# OLED.net
KiCad netlist of a schematic drawn in EAGLE
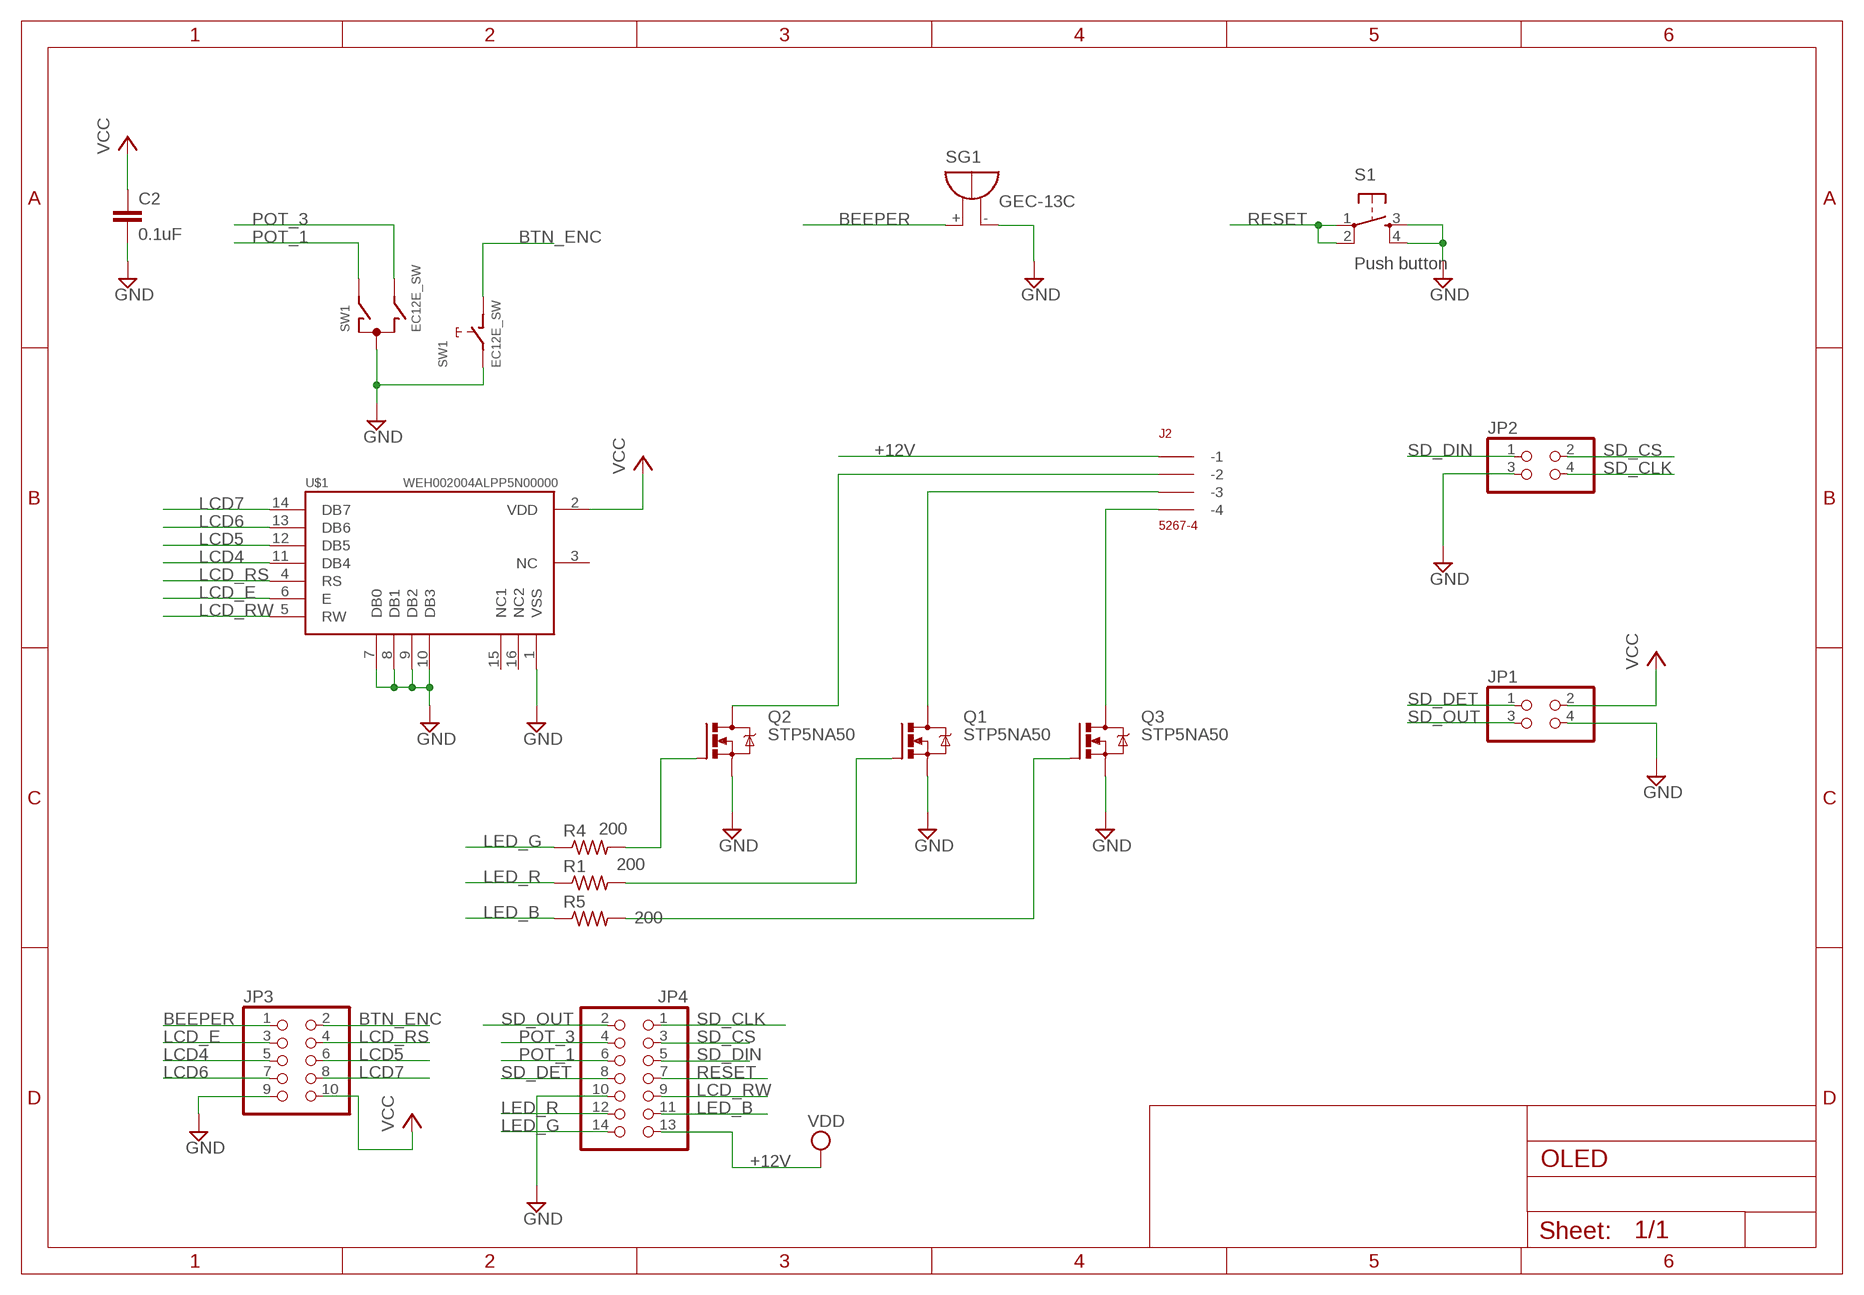
[diagram p0: schematic, sheet 1]

(export (version "E")
  (design (tool "Eeschema 10.0.6"))
  (components
    (comp (ref "C2")
      (value "0.1uF")
      (footprint "eagle-import:C0805")
      (libsource (lib "eagle-import") (part "C-EUC0805"))
    )
    (comp (ref "J2")
      (value "5267-4")
      (footprint "eagle-import:5267-4")
      (libsource (lib "eagle-import") (part "5267-4"))
    )
    (comp (ref "JP1")
      (value "PINHD-2X2")
      (footprint "eagle-import:2X02")
      (libsource (lib "eagle-import") (part "PINHD-2X2"))
    )
    (comp (ref "JP2")
      (value "PINHD-2X2")
      (footprint "eagle-import:2X02")
      (libsource (lib "eagle-import") (part "PINHD-2X2"))
    )
    (comp (ref "JP3")
      (value "PINHD-2X5/90")
      (footprint "eagle-import:2X05_90")
      (libsource (lib "eagle-import") (part "PINHD-2X5/90"))
    )
    (comp (ref "JP4")
      (value "PINHD-2X7/90")
      (footprint "eagle-import:2X07_90")
      (libsource (lib "eagle-import") (part "PINHD-2X7/90"))
    )
    (comp (ref "Q1")
      (value "STP5NA50")
      (footprint "eagle-import:TO220BV")
      (libsource (lib "eagle-import") (part "STP5NA50"))
    )
    (comp (ref "Q2")
      (value "STP5NA50")
      (footprint "eagle-import:TO220BV")
      (libsource (lib "eagle-import") (part "STP5NA50"))
    )
    (comp (ref "Q3")
      (value "STP5NA50")
      (footprint "eagle-import:TO220BV")
      (libsource (lib "eagle-import") (part "STP5NA50"))
    )
    (comp (ref "R1")
      (value "200")
      (footprint "eagle-import:R2012")
      (libsource (lib "eagle-import") (part "R-US_R2012"))
    )
    (comp (ref "R4")
      (value "200")
      (footprint "eagle-import:R2012")
      (libsource (lib "eagle-import") (part "R-US_R2012"))
    )
    (comp (ref "R5")
      (value "200")
      (footprint "eagle-import:R2012")
      (libsource (lib "eagle-import") (part "R-US_R2012"))
    )
    (comp (ref "S1")
      (value "Push button")
      (footprint "eagle-import:TACTILE-PTH")
      (libsource (lib "eagle-import") (part "TAC_SWITCHPTH"))
    )
    (comp (ref "SG1")
      (value "GEC-13C")
      (footprint "eagle-import:F_TMB")
      (libsource (lib "eagle-import") (part "F/TMB"))
    )
    (comp (ref "SW1")
      (value "EC12E_SW")
      (footprint "eagle-import:ALPS_EC12E_SW")
      (fields (field (name "MPN") "EC12E2424407"))
      (libsource (lib "eagle-import") (part "EC12E_SW"))
    )
    (comp (ref "U$1")
      (value "OLED")
      (footprint "eagle-import:WEH002004ALPP5N00000")
      (libsource (lib "eagle-import") (part "OLED"))
    )
  )
  (nets
    (net (code "1") (name "/BEEPER") (class "Default")
      (node (ref "JP3") (pin "1") (pinfunction "1_1") (pintype "passive"))
      (node (ref "SG1") (pin "+") (pinfunction "+_+") (pintype "passive"))
    )
    (net (code "2") (name "/BTN_ENC") (class "Default")
      (node (ref "JP3") (pin "2") (pinfunction "2_2") (pintype "passive"))
      (node (ref "SW1") (pin "D") (pinfunction "1_D") (pintype "passive"))
    )
    (net (code "3") (name "/LCD4") (class "Default")
      (node (ref "JP3") (pin "5") (pinfunction "5_5") (pintype "passive"))
      (node (ref "U$1") (pin "11") (pinfunction "DB4_11") (pintype "bidirectional"))
    )
    (net (code "4") (name "/LCD5") (class "Default")
      (node (ref "JP3") (pin "6") (pinfunction "6_6") (pintype "passive"))
      (node (ref "U$1") (pin "12") (pinfunction "DB5_12") (pintype "bidirectional"))
    )
    (net (code "5") (name "/LCD6") (class "Default")
      (node (ref "JP3") (pin "7") (pinfunction "7_7") (pintype "passive"))
      (node (ref "U$1") (pin "13") (pinfunction "DB6_13") (pintype "bidirectional"))
    )
    (net (code "6") (name "/LCD7") (class "Default")
      (node (ref "JP3") (pin "8") (pinfunction "8_8") (pintype "passive"))
      (node (ref "U$1") (pin "14") (pinfunction "DB7_14") (pintype "bidirectional"))
    )
    (net (code "7") (name "/LCD_E") (class "Default")
      (node (ref "JP3") (pin "3") (pinfunction "3_3") (pintype "passive"))
      (node (ref "U$1") (pin "6") (pinfunction "E_6") (pintype "bidirectional"))
    )
    (net (code "8") (name "/LCD_RS") (class "Default")
      (node (ref "JP3") (pin "4") (pinfunction "4_4") (pintype "passive"))
      (node (ref "U$1") (pin "4") (pinfunction "RS_4") (pintype "bidirectional"))
    )
    (net (code "9") (name "/LCD_RW") (class "Default")
      (node (ref "JP4") (pin "9") (pinfunction "9_9") (pintype "passive"))
      (node (ref "U$1") (pin "5") (pinfunction "RW_5") (pintype "bidirectional"))
    )
    (net (code "10") (name "/LED_B") (class "Default")
      (node (ref "JP4") (pin "11") (pinfunction "11_11") (pintype "passive"))
      (node (ref "R5") (pin "1") (pinfunction "1_1") (pintype "passive"))
    )
    (net (code "11") (name "/LED_G") (class "Default")
      (node (ref "JP4") (pin "14") (pinfunction "14_14") (pintype "passive"))
      (node (ref "R4") (pin "1") (pinfunction "1_1") (pintype "passive"))
    )
    (net (code "12") (name "/LED_R") (class "Default")
      (node (ref "JP4") (pin "12") (pinfunction "12_12") (pintype "passive"))
      (node (ref "R1") (pin "1") (pinfunction "1_1") (pintype "passive"))
    )
    (net (code "13") (name "/POT_1") (class "Default")
      (node (ref "JP4") (pin "6") (pinfunction "6_6") (pintype "passive"))
      (node (ref "SW1") (pin "A") (pinfunction "A_A") (pintype "passive"))
    )
    (net (code "14") (name "/POT_3") (class "Default")
      (node (ref "JP4") (pin "4") (pinfunction "4_4") (pintype "passive"))
      (node (ref "SW1") (pin "B") (pinfunction "B_B") (pintype "passive"))
    )
    (net (code "15") (name "/RESET") (class "Default")
      (node (ref "JP4") (pin "7") (pinfunction "7_7") (pintype "passive"))
      (node (ref "S1") (pin "1") (pinfunction "1_1") (pintype "passive"))
      (node (ref "S1") (pin "2") (pinfunction "2_2") (pintype "passive"))
    )
    (net (code "16") (name "/SD_CLK") (class "Default")
      (node (ref "JP2") (pin "4") (pinfunction "4_4") (pintype "passive"))
      (node (ref "JP4") (pin "1") (pinfunction "1_1") (pintype "passive"))
    )
    (net (code "17") (name "/SD_CS") (class "Default")
      (node (ref "JP2") (pin "2") (pinfunction "2_2") (pintype "passive"))
      (node (ref "JP4") (pin "3") (pinfunction "3_3") (pintype "passive"))
    )
    (net (code "18") (name "/SD_DET") (class "Default")
      (node (ref "JP1") (pin "1") (pinfunction "1_1") (pintype "passive"))
      (node (ref "JP4") (pin "8") (pinfunction "8_8") (pintype "passive"))
    )
    (net (code "19") (name "/SD_DIN") (class "Default")
      (node (ref "JP2") (pin "1") (pinfunction "1_1") (pintype "passive"))
      (node (ref "JP4") (pin "5") (pinfunction "5_5") (pintype "passive"))
    )
    (net (code "20") (name "/SD_OUT") (class "Default")
      (node (ref "JP1") (pin "3") (pinfunction "3_3") (pintype "passive"))
      (node (ref "JP4") (pin "2") (pinfunction "2_2") (pintype "passive"))
    )
    (net (code "21") (name "GND") (class "Default")
      (node (ref "C2") (pin "2") (pinfunction "2_2") (pintype "passive"))
      (node (ref "JP1") (pin "4") (pinfunction "4_4") (pintype "passive"))
      (node (ref "JP2") (pin "3") (pinfunction "3_3") (pintype "passive"))
      (node (ref "JP3") (pin "9") (pinfunction "9_9") (pintype "passive"))
      (node (ref "JP4") (pin "10") (pinfunction "10_10") (pintype "passive"))
      (node (ref "Q1") (pin "S") (pinfunction "S_S") (pintype "passive"))
      (node (ref "Q2") (pin "S") (pinfunction "S_S") (pintype "passive"))
      (node (ref "Q3") (pin "S") (pinfunction "S_S") (pintype "passive"))
      (node (ref "S1") (pin "3") (pinfunction "3_3") (pintype "passive"))
      (node (ref "S1") (pin "4") (pinfunction "4_4") (pintype "passive"))
      (node (ref "SG1") (pin "-") (pinfunction "-_-") (pintype "passive"))
      (node (ref "SW1") (pin "C") (pinfunction "C_C") (pintype "passive"))
      (node (ref "SW1") (pin "E") (pinfunction "2_E") (pintype "passive"))
      (node (ref "U$1") (pin "1") (pinfunction "VSS_1") (pintype "bidirectional"))
      (node (ref "U$1") (pin "10") (pinfunction "DB3_10") (pintype "bidirectional"))
      (node (ref "U$1") (pin "7") (pinfunction "DB0_7") (pintype "bidirectional"))
      (node (ref "U$1") (pin "8") (pinfunction "DB1_8") (pintype "bidirectional"))
      (node (ref "U$1") (pin "9") (pinfunction "DB2_9") (pintype "bidirectional"))
    )
    (net (code "22") (name "Net-(J2--2)") (class "Default")
      (node (ref "J2") (pin "P$2") (pinfunction "-2_P$2") (pintype "bidirectional"))
      (node (ref "Q2") (pin "D") (pinfunction "D_D") (pintype "passive"))
    )
    (net (code "23") (name "Net-(J2--3)") (class "Default")
      (node (ref "J2") (pin "P$3") (pinfunction "-3_P$3") (pintype "bidirectional"))
      (node (ref "Q1") (pin "D") (pinfunction "D_D") (pintype "passive"))
    )
    (net (code "24") (name "Net-(J2--4)") (class "Default")
      (node (ref "J2") (pin "P$4") (pinfunction "-4_P$4") (pintype "bidirectional"))
      (node (ref "Q3") (pin "D") (pinfunction "D_D") (pintype "passive"))
    )
    (net (code "25") (name "Net-(Q1-PadG)") (class "Default")
      (node (ref "Q1") (pin "G") (pinfunction "G_G") (pintype "passive"))
      (node (ref "R1") (pin "2") (pinfunction "2_2") (pintype "passive"))
    )
    (net (code "26") (name "Net-(Q2-PadG)") (class "Default")
      (node (ref "Q2") (pin "G") (pinfunction "G_G") (pintype "passive"))
      (node (ref "R4") (pin "2") (pinfunction "2_2") (pintype "passive"))
    )
    (net (code "27") (name "Net-(Q3-PadG)") (class "Default")
      (node (ref "Q3") (pin "G") (pinfunction "G_G") (pintype "passive"))
      (node (ref "R5") (pin "2") (pinfunction "2_2") (pintype "passive"))
    )
    (net (code "28") (name "VCC") (class "Default")
      (node (ref "C2") (pin "1") (pinfunction "1_1") (pintype "passive"))
      (node (ref "JP1") (pin "2") (pinfunction "2_2") (pintype "passive"))
      (node (ref "JP3") (pin "10") (pinfunction "10_10") (pintype "passive"))
      (node (ref "U$1") (pin "2") (pinfunction "VDD_2") (pintype "bidirectional"))
    )
    (net (code "29") (name "VDD") (class "Default")
      (node (ref "J2") (pin "P$1") (pinfunction "-1_P$1") (pintype "bidirectional"))
      (node (ref "JP4") (pin "13") (pinfunction "13_13") (pintype "passive"))
    )
    (net (code "30") (name "unconnected-(U$1-NC-Pad3)") (class "Default")
      (node (ref "U$1") (pin "3") (pinfunction "NC_3") (pintype "bidirectional"))
    )
    (net (code "31") (name "unconnected-(U$1-NC1-Pad15)") (class "Default")
      (node (ref "U$1") (pin "15") (pinfunction "NC1_15") (pintype "bidirectional"))
    )
    (net (code "32") (name "unconnected-(U$1-NC2-Pad16)") (class "Default")
      (node (ref "U$1") (pin "16") (pinfunction "NC2_16") (pintype "bidirectional"))
    )
  )
)
